# IotaWatt4_8.net
KiCad netlist of a schematic drawn in EAGLE
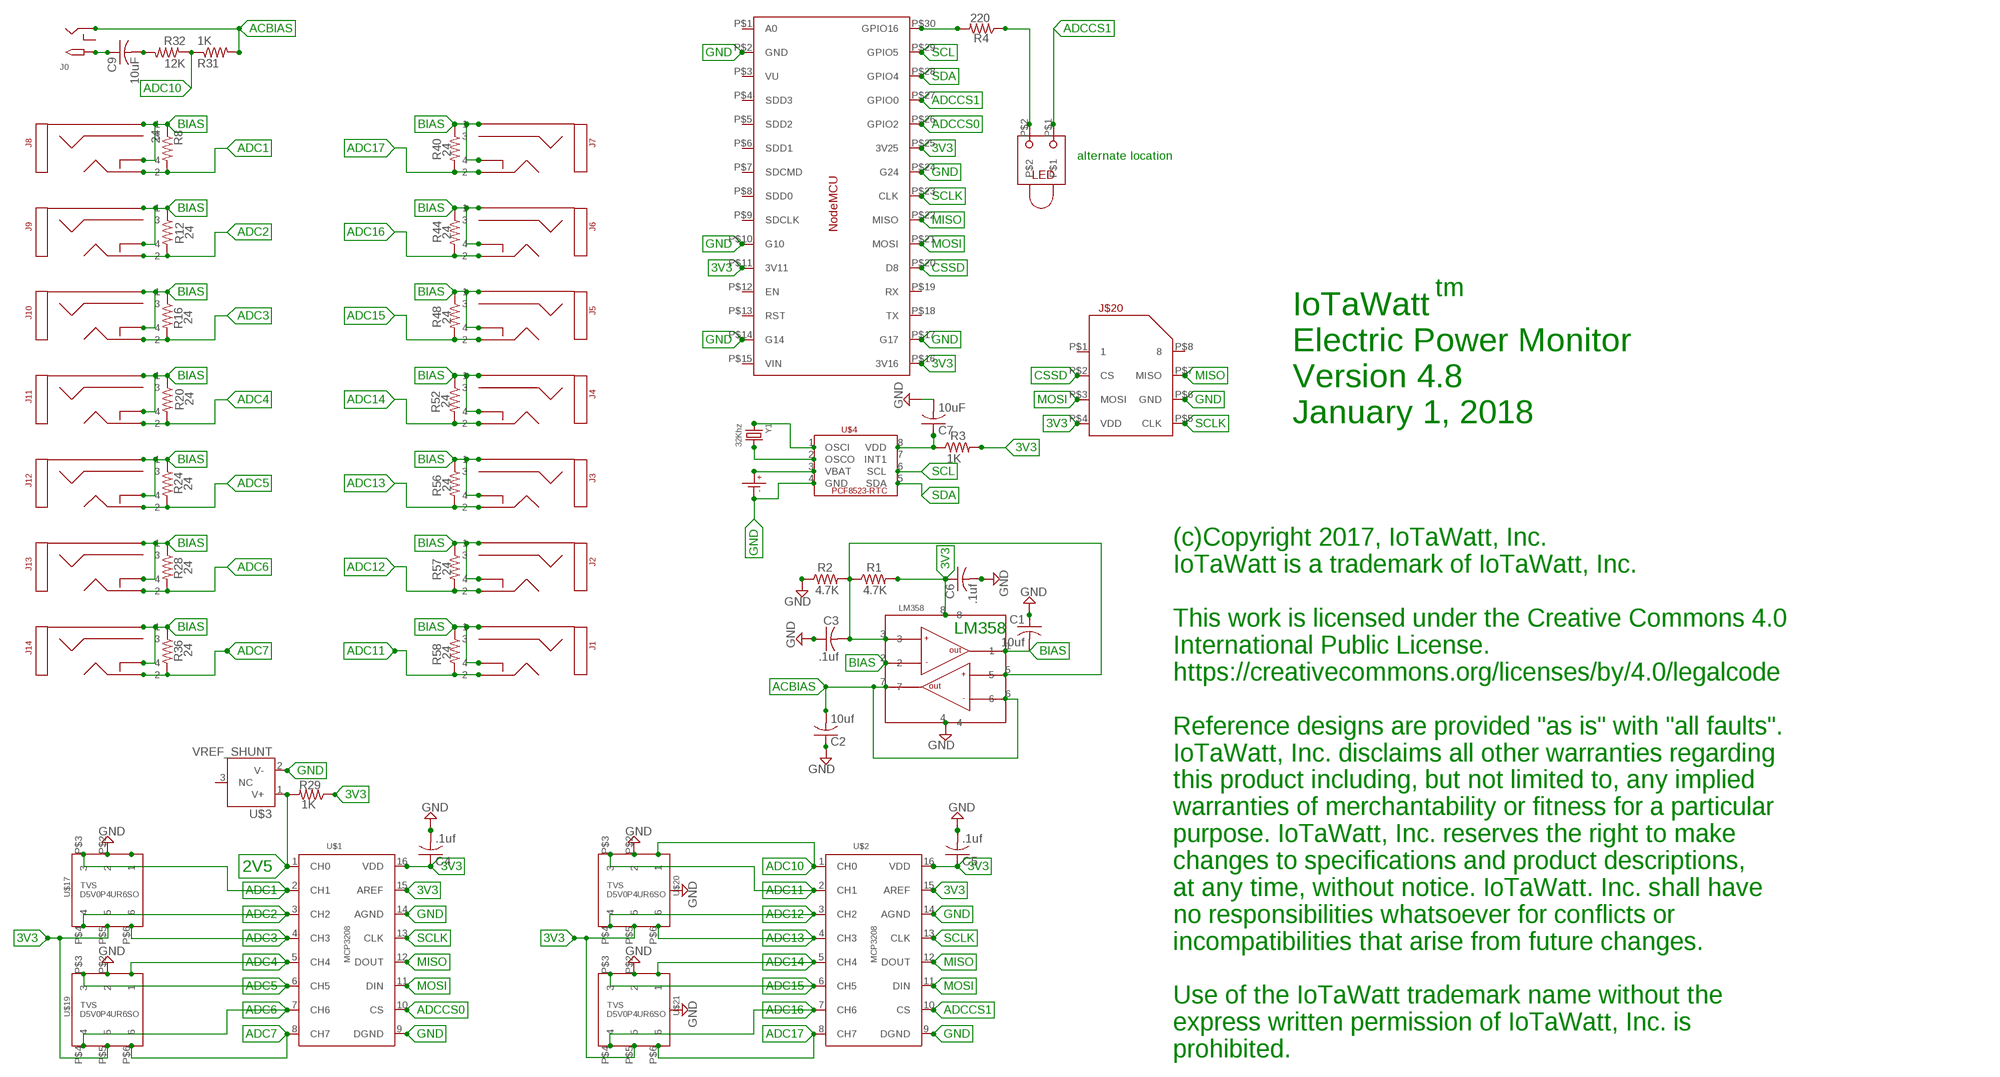
[diagram p0: schematic, sheet 1]

(export (version "E")
  (design (tool "Eeschema 10.0.6"))
  (components
    (comp (ref "C1")
      (value "10uf")
      (footprint "eagle-import:C0805")
      (libsource (lib "eagle-import") (part "C-USC0805"))
    )
    (comp (ref "C2")
      (value "10uf")
      (footprint "eagle-import:C0805")
      (libsource (lib "eagle-import") (part "C-USC0805"))
    )
    (comp (ref "C3")
      (value ".1uf")
      (footprint "eagle-import:C0805")
      (libsource (lib "eagle-import") (part "C-USC0805"))
    )
    (comp (ref "C4")
      (value ".1uf")
      (footprint "eagle-import:C0805")
      (libsource (lib "eagle-import") (part "C-USC0805"))
    )
    (comp (ref "C5")
      (value ".1uf")
      (footprint "eagle-import:C0805")
      (libsource (lib "eagle-import") (part "C-USC0805"))
    )
    (comp (ref "C6")
      (value ".1uf")
      (footprint "eagle-import:C0805")
      (libsource (lib "eagle-import") (part "C-USC0805"))
    )
    (comp (ref "C7")
      (value "10uF")
      (footprint "eagle-import:C0805")
      (libsource (lib "eagle-import") (part "C-USC0805"))
    )
    (comp (ref "C9")
      (value "10uF")
      (footprint "eagle-import:C0805")
      (libsource (lib "eagle-import") (part "C-USC0805"))
    )
    (comp (ref "J$20")
      (value "MICROSD_PUSH/PULL")
      (footprint "eagle-import:MICROSD")
      (libsource (lib "eagle-import") (part "MICROSD_PUSH/PULL"))
    )
    (comp (ref "J0")
      (value "2.1MMJACKSMT")
      (footprint "eagle-import:DCJACK_2MM_SMT")
      (libsource (lib "eagle-import") (part "2.1MMJACKSMT"))
    )
    (comp (ref "J1")
      (value "STEREO_SMD")
      (footprint "eagle-import:STEREO_SMT")
      (libsource (lib "eagle-import") (part "STEREO_SMD"))
    )
    (comp (ref "J2")
      (value "STEREO_SMD")
      (footprint "eagle-import:STEREO_SMT")
      (libsource (lib "eagle-import") (part "STEREO_SMD"))
    )
    (comp (ref "J3")
      (value "STEREO_SMD")
      (footprint "eagle-import:STEREO_SMT")
      (libsource (lib "eagle-import") (part "STEREO_SMD"))
    )
    (comp (ref "J4")
      (value "STEREO_SMD")
      (footprint "eagle-import:STEREO_SMT")
      (libsource (lib "eagle-import") (part "STEREO_SMD"))
    )
    (comp (ref "J5")
      (value "STEREO_SMD")
      (footprint "eagle-import:STEREO_SMT")
      (libsource (lib "eagle-import") (part "STEREO_SMD"))
    )
    (comp (ref "J6")
      (value "STEREO_SMD")
      (footprint "eagle-import:STEREO_SMT")
      (libsource (lib "eagle-import") (part "STEREO_SMD"))
    )
    (comp (ref "J7")
      (value "STEREO_SMD")
      (footprint "eagle-import:STEREO_SMT")
      (libsource (lib "eagle-import") (part "STEREO_SMD"))
    )
    (comp (ref "J8")
      (value "STEREO_SMD")
      (footprint "eagle-import:STEREO_SMT")
      (libsource (lib "eagle-import") (part "STEREO_SMD"))
    )
    (comp (ref "J9")
      (value "STEREO_SMD")
      (footprint "eagle-import:STEREO_SMT")
      (libsource (lib "eagle-import") (part "STEREO_SMD"))
    )
    (comp (ref "J10")
      (value "STEREO_SMD")
      (footprint "eagle-import:STEREO_SMT")
      (libsource (lib "eagle-import") (part "STEREO_SMD"))
    )
    (comp (ref "J11")
      (value "STEREO_SMD")
      (footprint "eagle-import:STEREO_SMT")
      (libsource (lib "eagle-import") (part "STEREO_SMD"))
    )
    (comp (ref "J12")
      (value "STEREO_SMD")
      (footprint "eagle-import:STEREO_SMT")
      (libsource (lib "eagle-import") (part "STEREO_SMD"))
    )
    (comp (ref "J13")
      (value "STEREO_SMD")
      (footprint "eagle-import:STEREO_SMT")
      (libsource (lib "eagle-import") (part "STEREO_SMD"))
    )
    (comp (ref "J14")
      (value "STEREO_SMD")
      (footprint "eagle-import:STEREO_SMT")
      (libsource (lib "eagle-import") (part "STEREO_SMD"))
    )
    (comp (ref "R1")
      (value "4.7K")
      (footprint "eagle-import:R0805")
      (libsource (lib "eagle-import") (part "R-US_R0805"))
    )
    (comp (ref "R2")
      (value "4.7K")
      (footprint "eagle-import:R0805")
      (libsource (lib "eagle-import") (part "R-US_R0805"))
    )
    (comp (ref "R3")
      (value "1K")
      (footprint "eagle-import:R0805")
      (libsource (lib "eagle-import") (part "R-US_R0805"))
    )
    (comp (ref "R4")
      (value "220")
      (footprint "eagle-import:R0805")
      (libsource (lib "eagle-import") (part "R-US_R0805"))
    )
    (comp (ref "R8")
      (value "24")
      (footprint "eagle-import:R0805")
      (libsource (lib "eagle-import") (part "R-US_R0805"))
    )
    (comp (ref "R12")
      (value "24")
      (footprint "eagle-import:R0805")
      (libsource (lib "eagle-import") (part "R-US_R0805"))
    )
    (comp (ref "R16")
      (value "24")
      (footprint "eagle-import:R0805")
      (libsource (lib "eagle-import") (part "R-US_R0805"))
    )
    (comp (ref "R20")
      (value "24")
      (footprint "eagle-import:R0805")
      (libsource (lib "eagle-import") (part "R-US_R0805"))
    )
    (comp (ref "R24")
      (value "24")
      (footprint "eagle-import:R0805")
      (libsource (lib "eagle-import") (part "R-US_R0805"))
    )
    (comp (ref "R28")
      (value "24")
      (footprint "eagle-import:R0805")
      (libsource (lib "eagle-import") (part "R-US_R0805"))
    )
    (comp (ref "R29")
      (value "1K")
      (footprint "eagle-import:R0805")
      (libsource (lib "eagle-import") (part "R-US_R0805"))
    )
    (comp (ref "R31")
      (value "1K")
      (footprint "eagle-import:R0805")
      (libsource (lib "eagle-import") (part "R-US_R0805"))
    )
    (comp (ref "R32")
      (value "12K")
      (footprint "eagle-import:R0805")
      (libsource (lib "eagle-import") (part "R-US_R0805"))
    )
    (comp (ref "R36")
      (value "24")
      (footprint "eagle-import:R0805")
      (libsource (lib "eagle-import") (part "R-US_R0805"))
    )
    (comp (ref "R40")
      (value "24")
      (footprint "eagle-import:R0805")
      (libsource (lib "eagle-import") (part "R-US_R0805"))
    )
    (comp (ref "R44")
      (value "24")
      (footprint "eagle-import:R0805")
      (libsource (lib "eagle-import") (part "R-US_R0805"))
    )
    (comp (ref "R48")
      (value "24")
      (footprint "eagle-import:R0805")
      (libsource (lib "eagle-import") (part "R-US_R0805"))
    )
    (comp (ref "R52")
      (value "24")
      (footprint "eagle-import:R0805")
      (libsource (lib "eagle-import") (part "R-US_R0805"))
    )
    (comp (ref "R56")
      (value "24")
      (footprint "eagle-import:R0805")
      (libsource (lib "eagle-import") (part "R-US_R0805"))
    )
    (comp (ref "R57")
      (value "24")
      (footprint "eagle-import:R0805")
      (libsource (lib "eagle-import") (part "R-US_R0805"))
    )
    (comp (ref "R58")
      (value "24")
      (footprint "eagle-import:R0805")
      (libsource (lib "eagle-import") (part "R-US_R0805"))
    )
    (comp (ref "U$1")
      (value "MCP3208")
      (footprint "eagle-import:SOIC_16")
      (libsource (lib "eagle-import") (part "MCP3208"))
    )
    (comp (ref "U$2")
      (value "MCP3208")
      (footprint "eagle-import:SOIC_16")
      (libsource (lib "eagle-import") (part "MCP3208"))
    )
    (comp (ref "U$3")
      (value "VREF_SHUNT")
      (footprint "eagle-import:SOT23_3")
      (libsource (lib "eagle-import") (part "VREF_SHUNT"))
    )
    (comp (ref "U$4")
      (value "PCF8523_RTC")
      (footprint "eagle-import:SOIC_8")
      (libsource (lib "eagle-import") (part "PCF8523_RTC"))
    )
    (comp (ref "U$16")
      (value "NODEMCU")
      (footprint "eagle-import:NODEMCU")
      (libsource (lib "eagle-import") (part "NODEMCU"))
    )
    (comp (ref "U$17")
      (value "TVS_4CHAN_ARRAYSC-74")
      (footprint "eagle-import:SC-74")
      (libsource (lib "eagle-import") (part "TVS_4CHAN_ARRAYSC-74"))
    )
    (comp (ref "U$18")
      (value "CR1220SMD")
      (footprint "eagle-import:CR1220SMD")
      (libsource (lib "eagle-import") (part "CR1220SMD"))
    )
    (comp (ref "U$19")
      (value "TVS_4CHAN_ARRAYSC-74")
      (footprint "eagle-import:SC-74")
      (libsource (lib "eagle-import") (part "TVS_4CHAN_ARRAYSC-74"))
    )
    (comp (ref "U$20")
      (value "TVS_4CHAN_ARRAYSC-74")
      (footprint "eagle-import:SC-74")
      (libsource (lib "eagle-import") (part "TVS_4CHAN_ARRAYSC-74"))
    )
    (comp (ref "U$21")
      (value "TVS_4CHAN_ARRAYSC-74")
      (footprint "eagle-import:SC-74")
      (libsource (lib "eagle-import") (part "TVS_4CHAN_ARRAYSC-74"))
    )
    (comp (ref "U$22")
      (value "LM358_DUAL_OP-AMP")
      (footprint "eagle-import:SOIC_8")
      (libsource (lib "eagle-import") (part "LM358_DUAL_OP-AMP"))
    )
    (comp (ref "U$23")
      (value "LED_RT_TRH")
      (footprint "eagle-import:LED_TH_RT")
      (libsource (lib "eagle-import") (part "LED_RT_TRH"))
    )
    (comp (ref "Y1")
      (value "32Khz")
      (footprint "eagle-import:CRYSTAL_8X3.8")
      (libsource (lib "eagle-import") (part "CRYSTAL8X3.8SMT"))
    )
  )
  (nets
    (net (code "1") (name "2V5") (class "Default")
      (node (ref "R29") (pin "2") (pinfunction "2_2") (pintype "passive"))
      (node (ref "U$1") (pin "1") (pinfunction "CH0_1") (pintype "input"))
      (node (ref "U$3") (pin "1") (pinfunction "V+_1") (pintype "bidirectional"))
    )
    (net (code "2") (name "3V3") (class "Default")
      (node (ref "C4") (pin "1") (pinfunction "1_1") (pintype "passive"))
      (node (ref "C5") (pin "1") (pinfunction "1_1") (pintype "passive"))
      (node (ref "C6") (pin "1") (pinfunction "1_1") (pintype "passive"))
      (node (ref "J$20") (pin "P$4") (pinfunction "VDD_P$4") (pintype "bidirectional"))
      (node (ref "R1") (pin "2") (pinfunction "2_2") (pintype "passive"))
      (node (ref "R29") (pin "1") (pinfunction "1_1") (pintype "passive"))
      (node (ref "R3") (pin "2") (pinfunction "2_2") (pintype "passive"))
      (node (ref "U$1") (pin "15") (pinfunction "AREF_15") (pintype "input"))
      (node (ref "U$1") (pin "16") (pinfunction "VDD_16") (pintype "bidirectional"))
      (node (ref "U$16") (pin "P$11") (pinfunction "3V11_P$11") (pintype "bidirectional"))
      (node (ref "U$16") (pin "P$16") (pinfunction "3V16_P$16") (pintype "bidirectional"))
      (node (ref "U$16") (pin "P$25") (pinfunction "3V25_P$25") (pintype "bidirectional"))
      (node (ref "U$17") (pin "P$5") (pinfunction "5_P$5") (pintype "bidirectional"))
      (node (ref "U$19") (pin "P$5") (pinfunction "5_P$5") (pintype "bidirectional"))
      (node (ref "U$2") (pin "15") (pinfunction "AREF_15") (pintype "input"))
      (node (ref "U$2") (pin "16") (pinfunction "VDD_16") (pintype "bidirectional"))
      (node (ref "U$20") (pin "P$5") (pinfunction "5_P$5") (pintype "bidirectional"))
      (node (ref "U$21") (pin "P$5") (pinfunction "5_P$5") (pintype "bidirectional"))
      (node (ref "U$22") (pin "8") (pinfunction "8_8") (pintype "bidirectional"))
    )
    (net (code "3") (name "ACBIAS") (class "Default")
      (node (ref "C2") (pin "2") (pinfunction "2_2") (pintype "passive"))
      (node (ref "J0") (pin "GND") (pinfunction "RING_GND") (pintype "bidirectional"))
      (node (ref "R31") (pin "2") (pinfunction "2_2") (pintype "passive"))
      (node (ref "U$22") (pin "6") (pinfunction "6_6") (pintype "bidirectional"))
      (node (ref "U$22") (pin "7") (pinfunction "7_7") (pintype "bidirectional"))
    )
    (net (code "4") (name "ADC1") (class "Default")
      (node (ref "J8") (pin "P$2") (pinfunction "2_P$2") (pintype "bidirectional"))
      (node (ref "R8") (pin "2") (pinfunction "2_2") (pintype "passive"))
      (node (ref "U$1") (pin "2") (pinfunction "CH1_2") (pintype "input"))
      (node (ref "U$17") (pin "P$3") (pinfunction "3_P$3") (pintype "bidirectional"))
    )
    (net (code "5") (name "ADC2") (class "Default")
      (node (ref "J9") (pin "P$2") (pinfunction "2_P$2") (pintype "bidirectional"))
      (node (ref "R12") (pin "2") (pinfunction "2_2") (pintype "passive"))
      (node (ref "U$1") (pin "3") (pinfunction "CH2_3") (pintype "input"))
      (node (ref "U$17") (pin "P$4") (pinfunction "4_P$4") (pintype "bidirectional"))
    )
    (net (code "6") (name "ADC3") (class "Default")
      (node (ref "J10") (pin "P$2") (pinfunction "2_P$2") (pintype "bidirectional"))
      (node (ref "R16") (pin "2") (pinfunction "2_2") (pintype "passive"))
      (node (ref "U$1") (pin "4") (pinfunction "CH3_4") (pintype "input"))
      (node (ref "U$17") (pin "P$6") (pinfunction "6_P$6") (pintype "bidirectional"))
    )
    (net (code "7") (name "ADC4") (class "Default")
      (node (ref "J11") (pin "P$2") (pinfunction "2_P$2") (pintype "bidirectional"))
      (node (ref "R20") (pin "2") (pinfunction "2_2") (pintype "passive"))
      (node (ref "U$1") (pin "5") (pinfunction "CH4_5") (pintype "bidirectional"))
      (node (ref "U$19") (pin "P$1") (pinfunction "1_P$1") (pintype "bidirectional"))
    )
    (net (code "8") (name "ADC5") (class "Default")
      (node (ref "J12") (pin "P$2") (pinfunction "2_P$2") (pintype "bidirectional"))
      (node (ref "R24") (pin "2") (pinfunction "2_2") (pintype "passive"))
      (node (ref "U$1") (pin "6") (pinfunction "CH5_6") (pintype "bidirectional"))
      (node (ref "U$19") (pin "P$3") (pinfunction "3_P$3") (pintype "bidirectional"))
    )
    (net (code "9") (name "ADC6") (class "Default")
      (node (ref "J13") (pin "P$2") (pinfunction "2_P$2") (pintype "bidirectional"))
      (node (ref "R28") (pin "2") (pinfunction "2_2") (pintype "passive"))
      (node (ref "U$1") (pin "7") (pinfunction "CH6_7") (pintype "input"))
      (node (ref "U$19") (pin "P$4") (pinfunction "4_P$4") (pintype "bidirectional"))
    )
    (net (code "10") (name "ADC7") (class "Default")
      (node (ref "J14") (pin "P$2") (pinfunction "2_P$2") (pintype "bidirectional"))
      (node (ref "R36") (pin "2") (pinfunction "2_2") (pintype "passive"))
      (node (ref "U$1") (pin "8") (pinfunction "CH7_8") (pintype "bidirectional"))
      (node (ref "U$19") (pin "P$6") (pinfunction "6_P$6") (pintype "bidirectional"))
    )
    (net (code "11") (name "ADC10") (class "Default")
      (node (ref "R31") (pin "1") (pinfunction "1_1") (pintype "passive"))
      (node (ref "R32") (pin "1") (pinfunction "1_1") (pintype "passive"))
      (node (ref "U$2") (pin "1") (pinfunction "CH0_1") (pintype "input"))
      (node (ref "U$20") (pin "P$1") (pinfunction "1_P$1") (pintype "bidirectional"))
    )
    (net (code "12") (name "ADC11") (class "Default")
      (node (ref "J1") (pin "P$2") (pinfunction "2_P$2") (pintype "bidirectional"))
      (node (ref "R58") (pin "2") (pinfunction "2_2") (pintype "passive"))
      (node (ref "U$2") (pin "2") (pinfunction "CH1_2") (pintype "input"))
      (node (ref "U$20") (pin "P$3") (pinfunction "3_P$3") (pintype "bidirectional"))
    )
    (net (code "13") (name "ADC12") (class "Default")
      (node (ref "J2") (pin "P$2") (pinfunction "2_P$2") (pintype "bidirectional"))
      (node (ref "R57") (pin "2") (pinfunction "2_2") (pintype "passive"))
      (node (ref "U$2") (pin "3") (pinfunction "CH2_3") (pintype "input"))
      (node (ref "U$20") (pin "P$4") (pinfunction "4_P$4") (pintype "bidirectional"))
    )
    (net (code "14") (name "ADC13") (class "Default")
      (node (ref "J3") (pin "P$2") (pinfunction "2_P$2") (pintype "bidirectional"))
      (node (ref "R56") (pin "2") (pinfunction "2_2") (pintype "passive"))
      (node (ref "U$2") (pin "4") (pinfunction "CH3_4") (pintype "input"))
      (node (ref "U$20") (pin "P$6") (pinfunction "6_P$6") (pintype "bidirectional"))
    )
    (net (code "15") (name "ADC14") (class "Default")
      (node (ref "J4") (pin "P$2") (pinfunction "2_P$2") (pintype "bidirectional"))
      (node (ref "R52") (pin "2") (pinfunction "2_2") (pintype "passive"))
      (node (ref "U$2") (pin "5") (pinfunction "CH4_5") (pintype "bidirectional"))
      (node (ref "U$21") (pin "P$1") (pinfunction "1_P$1") (pintype "bidirectional"))
    )
    (net (code "16") (name "ADC15") (class "Default")
      (node (ref "J5") (pin "P$2") (pinfunction "2_P$2") (pintype "bidirectional"))
      (node (ref "R48") (pin "2") (pinfunction "2_2") (pintype "passive"))
      (node (ref "U$2") (pin "6") (pinfunction "CH5_6") (pintype "bidirectional"))
      (node (ref "U$21") (pin "P$3") (pinfunction "3_P$3") (pintype "bidirectional"))
    )
    (net (code "17") (name "ADC16") (class "Default")
      (node (ref "J6") (pin "P$2") (pinfunction "2_P$2") (pintype "bidirectional"))
      (node (ref "R44") (pin "2") (pinfunction "2_2") (pintype "passive"))
      (node (ref "U$2") (pin "7") (pinfunction "CH6_7") (pintype "input"))
      (node (ref "U$21") (pin "P$4") (pinfunction "4_P$4") (pintype "bidirectional"))
    )
    (net (code "18") (name "ADC17") (class "Default")
      (node (ref "J7") (pin "P$2") (pinfunction "2_P$2") (pintype "bidirectional"))
      (node (ref "R40") (pin "2") (pinfunction "2_2") (pintype "passive"))
      (node (ref "U$2") (pin "8") (pinfunction "CH7_8") (pintype "bidirectional"))
      (node (ref "U$21") (pin "P$6") (pinfunction "6_P$6") (pintype "bidirectional"))
    )
    (net (code "19") (name "ADCCS0") (class "Default")
      (node (ref "U$1") (pin "10") (pinfunction "CS_10") (pintype "input"))
      (node (ref "U$16") (pin "P$26") (pinfunction "GPIO2_P$26") (pintype "bidirectional"))
    )
    (net (code "20") (name "ADCCS1") (class "Default")
      (node (ref "U$16") (pin "P$27") (pinfunction "GPIO0_P$27") (pintype "bidirectional"))
      (node (ref "U$2") (pin "10") (pinfunction "CS_10") (pintype "input"))
      (node (ref "U$23") (pin "P$1") (pinfunction "P$1_P$1") (pintype "bidirectional"))
    )
    (net (code "21") (name "BIAS") (class "Default")
      (node (ref "C1") (pin "2") (pinfunction "2_2") (pintype "passive"))
      (node (ref "J1") (pin "P$1") (pinfunction "1_P$1") (pintype "bidirectional"))
      (node (ref "J1") (pin "P$4") (pinfunction "4_P$4") (pintype "bidirectional"))
      (node (ref "J10") (pin "P$1") (pinfunction "1_P$1") (pintype "bidirectional"))
      (node (ref "J10") (pin "P$4") (pinfunction "4_P$4") (pintype "bidirectional"))
      (node (ref "J11") (pin "P$1") (pinfunction "1_P$1") (pintype "bidirectional"))
      (node (ref "J11") (pin "P$4") (pinfunction "4_P$4") (pintype "bidirectional"))
      (node (ref "J12") (pin "P$1") (pinfunction "1_P$1") (pintype "bidirectional"))
      (node (ref "J12") (pin "P$4") (pinfunction "4_P$4") (pintype "bidirectional"))
      (node (ref "J13") (pin "P$1") (pinfunction "1_P$1") (pintype "bidirectional"))
      (node (ref "J13") (pin "P$4") (pinfunction "4_P$4") (pintype "bidirectional"))
      (node (ref "J14") (pin "P$1") (pinfunction "1_P$1") (pintype "bidirectional"))
      (node (ref "J14") (pin "P$4") (pinfunction "4_P$4") (pintype "bidirectional"))
      (node (ref "J2") (pin "P$1") (pinfunction "1_P$1") (pintype "bidirectional"))
      (node (ref "J2") (pin "P$4") (pinfunction "4_P$4") (pintype "bidirectional"))
      (node (ref "J3") (pin "P$1") (pinfunction "1_P$1") (pintype "bidirectional"))
      (node (ref "J3") (pin "P$4") (pinfunction "4_P$4") (pintype "bidirectional"))
      (node (ref "J4") (pin "P$1") (pinfunction "1_P$1") (pintype "bidirectional"))
      (node (ref "J4") (pin "P$4") (pinfunction "4_P$4") (pintype "bidirectional"))
      (node (ref "J5") (pin "P$1") (pinfunction "1_P$1") (pintype "bidirectional"))
      (node (ref "J5") (pin "P$4") (pinfunction "4_P$4") (pintype "bidirectional"))
      (node (ref "J6") (pin "P$1") (pinfunction "1_P$1") (pintype "bidirectional"))
      (node (ref "J6") (pin "P$4") (pinfunction "4_P$4") (pintype "bidirectional"))
      (node (ref "J7") (pin "P$1") (pinfunction "1_P$1") (pintype "bidirectional"))
      (node (ref "J7") (pin "P$4") (pinfunction "4_P$4") (pintype "bidirectional"))
      (node (ref "J8") (pin "P$1") (pinfunction "1_P$1") (pintype "bidirectional"))
      (node (ref "J8") (pin "P$4") (pinfunction "4_P$4") (pintype "bidirectional"))
      (node (ref "J9") (pin "P$1") (pinfunction "1_P$1") (pintype "bidirectional"))
      (node (ref "J9") (pin "P$4") (pinfunction "4_P$4") (pintype "bidirectional"))
      (node (ref "R12") (pin "1") (pinfunction "1_1") (pintype "passive"))
      (node (ref "R16") (pin "1") (pinfunction "1_1") (pintype "passive"))
      (node (ref "R20") (pin "1") (pinfunction "1_1") (pintype "passive"))
      (node (ref "R24") (pin "1") (pinfunction "1_1") (pintype "passive"))
      (node (ref "R28") (pin "1") (pinfunction "1_1") (pintype "passive"))
      (node (ref "R36") (pin "1") (pinfunction "1_1") (pintype "passive"))
      (node (ref "R40") (pin "1") (pinfunction "1_1") (pintype "passive"))
      (node (ref "R44") (pin "1") (pinfunction "1_1") (pintype "passive"))
      (node (ref "R48") (pin "1") (pinfunction "1_1") (pintype "passive"))
      (node (ref "R52") (pin "1") (pinfunction "1_1") (pintype "passive"))
      (node (ref "R56") (pin "1") (pinfunction "1_1") (pintype "passive"))
      (node (ref "R57") (pin "1") (pinfunction "1_1") (pintype "passive"))
      (node (ref "R58") (pin "1") (pinfunction "1_1") (pintype "passive"))
      (node (ref "R8") (pin "1") (pinfunction "1_1") (pintype "passive"))
      (node (ref "U$22") (pin "1") (pinfunction "1_1") (pintype "bidirectional"))
      (node (ref "U$22") (pin "2") (pinfunction "2_2") (pintype "bidirectional"))
    )
    (net (code "22") (name "CSSD") (class "Default")
      (node (ref "J$20") (pin "P$2") (pinfunction "CS_P$2") (pintype "bidirectional"))
      (node (ref "U$16") (pin "P$20") (pinfunction "D8_P$20") (pintype "bidirectional"))
    )
    (net (code "23") (name "GND") (class "Default")
      (node (ref "C1") (pin "1") (pinfunction "1_1") (pintype "passive"))
      (node (ref "C2") (pin "1") (pinfunction "1_1") (pintype "passive"))
      (node (ref "C3") (pin "1") (pinfunction "1_1") (pintype "passive"))
      (node (ref "C4") (pin "2") (pinfunction "2_2") (pintype "passive"))
      (node (ref "C5") (pin "2") (pinfunction "2_2") (pintype "passive"))
      (node (ref "C6") (pin "2") (pinfunction "2_2") (pintype "passive"))
      (node (ref "C7") (pin "2") (pinfunction "2_2") (pintype "passive"))
      (node (ref "J$20") (pin "P$6") (pinfunction "GND_P$6") (pintype "bidirectional"))
      (node (ref "R2") (pin "1") (pinfunction "1_1") (pintype "passive"))
      (node (ref "U$1") (pin "14") (pinfunction "AGND_14") (pintype "input"))
      (node (ref "U$1") (pin "9") (pinfunction "DGND_9") (pintype "bidirectional"))
      (node (ref "U$16") (pin "P$10") (pinfunction "G10_P$10") (pintype "bidirectional"))
      (node (ref "U$16") (pin "P$14") (pinfunction "G14_P$14") (pintype "bidirectional"))
      (node (ref "U$16") (pin "P$17") (pinfunction "G17_P$17") (pintype "bidirectional"))
      (node (ref "U$16") (pin "P$2") (pinfunction "GND_P$2") (pintype "bidirectional"))
      (node (ref "U$16") (pin "P$24") (pinfunction "G24_P$24") (pintype "bidirectional"))
      (node (ref "U$17") (pin "P$2") (pinfunction "2_P$2") (pintype "bidirectional"))
      (node (ref "U$18") (pin "P-") (pinfunction "P$-_P-") (pintype "bidirectional"))
      (node (ref "U$19") (pin "P$2") (pinfunction "2_P$2") (pintype "bidirectional"))
      (node (ref "U$2") (pin "14") (pinfunction "AGND_14") (pintype "input"))
      (node (ref "U$2") (pin "9") (pinfunction "DGND_9") (pintype "bidirectional"))
      (node (ref "U$20") (pin "P$2") (pinfunction "2_P$2") (pintype "bidirectional"))
      (node (ref "U$21") (pin "P$2") (pinfunction "2_P$2") (pintype "bidirectional"))
      (node (ref "U$22") (pin "4") (pinfunction "4_4") (pintype "bidirectional"))
      (node (ref "U$3") (pin "2") (pinfunction "V-_2") (pintype "bidirectional"))
      (node (ref "U$4") (pin "4") (pinfunction "GND_4") (pintype "bidirectional"))
    )
    (net (code "24") (name "MISO") (class "Default")
      (node (ref "J$20") (pin "P$7") (pinfunction "MISO_P$7") (pintype "bidirectional"))
      (node (ref "U$1") (pin "12") (pinfunction "DOUT_12") (pintype "bidirectional"))
      (node (ref "U$16") (pin "P$22") (pinfunction "MISO_P$22") (pintype "bidirectional"))
      (node (ref "U$2") (pin "12") (pinfunction "DOUT_12") (pintype "bidirectional"))
    )
    (net (code "25") (name "MOSI") (class "Default")
      (node (ref "J$20") (pin "P$3") (pinfunction "MOSI_P$3") (pintype "bidirectional"))
      (node (ref "U$1") (pin "11") (pinfunction "DIN_11") (pintype "input"))
      (node (ref "U$16") (pin "P$21") (pinfunction "MOSI_P$21") (pintype "bidirectional"))
      (node (ref "U$2") (pin "11") (pinfunction "DIN_11") (pintype "input"))
    )
    (net (code "26") (name "Net-(C3-Pad2)") (class "Default")
      (node (ref "C3") (pin "2") (pinfunction "2_2") (pintype "passive"))
      (node (ref "R1") (pin "1") (pinfunction "1_1") (pintype "passive"))
      (node (ref "R2") (pin "2") (pinfunction "2_2") (pintype "passive"))
      (node (ref "U$22") (pin "3") (pinfunction "3_3") (pintype "bidirectional"))
      (node (ref "U$22") (pin "5") (pinfunction "5_5") (pintype "bidirectional"))
    )
    (net (code "27") (name "Net-(C9-Pad2)") (class "Default")
      (node (ref "C9") (pin "2") (pinfunction "2_2") (pintype "passive"))
      (node (ref "R32") (pin "2") (pinfunction "2_2") (pintype "passive"))
    )
    (net (code "28") (name "Net-(J0-TIP)") (class "Default")
      (node (ref "C9") (pin "1") (pinfunction "1_1") (pintype "passive"))
      (node (ref "J0") (pin "PWR2") (pinfunction "TIP_PWR2") (pintype "bidirectional"))
    )
    (net (code "29") (name "Net-(R4-Pad1)") (class "Default")
      (node (ref "R4") (pin "1") (pinfunction "1_1") (pintype "passive"))
      (node (ref "U$23") (pin "P$2") (pinfunction "P$2_P$2") (pintype "bidirectional"))
    )
    (net (code "30") (name "Net-(U$4-OSCI)") (class "Default")
      (node (ref "U$4") (pin "1") (pinfunction "OSCI_1") (pintype "bidirectional"))
      (node (ref "Y1") (pin "P$1") (pinfunction "1_P$1") (pintype "passive"))
    )
    (net (code "31") (name "Net-(U$4-OSCO)") (class "Default")
      (node (ref "U$4") (pin "2") (pinfunction "OSCO_2") (pintype "bidirectional"))
      (node (ref "Y1") (pin "P$4") (pinfunction "2_P$4") (pintype "passive"))
    )
    (net (code "32") (name "Net-(U$4-VDD)") (class "Default")
      (node (ref "C7") (pin "1") (pinfunction "1_1") (pintype "passive"))
      (node (ref "R3") (pin "1") (pinfunction "1_1") (pintype "passive"))
      (node (ref "U$4") (pin "8") (pinfunction "VDD_8") (pintype "bidirectional"))
    )
    (net (code "33") (name "Net-(U$16-GPIO16)") (class "Default")
      (node (ref "R4") (pin "2") (pinfunction "2_2") (pintype "passive"))
      (node (ref "U$16") (pin "P$30") (pinfunction "GPIO16_P$30") (pintype "bidirectional"))
    )
    (net (code "34") (name "Net-(U$18-P$+)") (class "Default")
      (node (ref "U$18") (pin "P+") (pinfunction "P$+_P+") (pintype "bidirectional"))
      (node (ref "U$4") (pin "3") (pinfunction "VBAT_3") (pintype "bidirectional"))
    )
    (net (code "35") (name "SCL") (class "Default")
      (node (ref "U$16") (pin "P$29") (pinfunction "GPIO5_P$29") (pintype "bidirectional"))
      (node (ref "U$4") (pin "6") (pinfunction "SCL_6") (pintype "bidirectional"))
    )
    (net (code "36") (name "SCLK") (class "Default")
      (node (ref "J$20") (pin "P$5") (pinfunction "CLK_P$5") (pintype "bidirectional"))
      (node (ref "U$1") (pin "13") (pinfunction "CLK_13") (pintype "input"))
      (node (ref "U$16") (pin "P$23") (pinfunction "CLK_P$23") (pintype "bidirectional"))
      (node (ref "U$2") (pin "13") (pinfunction "CLK_13") (pintype "input"))
    )
    (net (code "37") (name "SDA") (class "Default")
      (node (ref "U$16") (pin "P$28") (pinfunction "GPIO4_P$28") (pintype "bidirectional"))
      (node (ref "U$4") (pin "5") (pinfunction "SDA_5") (pintype "bidirectional"))
    )
    (net (code "38") (name "unconnected-(J$20-1-PadP$1)") (class "Default")
      (node (ref "J$20") (pin "P$1") (pinfunction "1_P$1") (pintype "bidirectional"))
    )
    (net (code "39") (name "unconnected-(J$20-8-PadP$8)") (class "Default")
      (node (ref "J$20") (pin "P$8") (pinfunction "8_P$8") (pintype "bidirectional"))
    )
    (net (code "40") (name "unconnected-(J0-RING_SW-PadGNDBREAK)") (class "Default")
      (node (ref "J0") (pin "GNDBREAK") (pinfunction "RING_SW_GNDBREAK") (pintype "bidirectional"))
    )
    (net (code "41") (name "unconnected-(J1-3-PadP$3)") (class "Default")
      (node (ref "J1") (pin "P$3") (pinfunction "3_P$3") (pintype "bidirectional"))
    )
    (net (code "42") (name "unconnected-(J2-3-PadP$3)") (class "Default")
      (node (ref "J2") (pin "P$3") (pinfunction "3_P$3") (pintype "bidirectional"))
    )
    (net (code "43") (name "unconnected-(J3-3-PadP$3)") (class "Default")
      (node (ref "J3") (pin "P$3") (pinfunction "3_P$3") (pintype "bidirectional"))
    )
    (net (code "44") (name "unconnected-(J4-3-PadP$3)") (class "Default")
      (node (ref "J4") (pin "P$3") (pinfunction "3_P$3") (pintype "bidirectional"))
    )
    (net (code "45") (name "unconnected-(J5-3-PadP$3)") (class "Default")
      (node (ref "J5") (pin "P$3") (pinfunction "3_P$3") (pintype "bidirectional"))
    )
    (net (code "46") (name "unconnected-(J6-3-PadP$3)") (class "Default")
      (node (ref "J6") (pin "P$3") (pinfunction "3_P$3") (pintype "bidirectional"))
    )
    (net (code "47") (name "unconnected-(J7-3-PadP$3)") (class "Default")
      (node (ref "J7") (pin "P$3") (pinfunction "3_P$3") (pintype "bidirectional"))
    )
    (net (code "48") (name "unconnected-(J8-3-PadP$3)") (class "Default")
      (node (ref "J8") (pin "P$3") (pinfunction "3_P$3") (pintype "bidirectional"))
    )
    (net (code "49") (name "unconnected-(J9-3-PadP$3)") (class "Default")
      (node (ref "J9") (pin "P$3") (pinfunction "3_P$3") (pintype "bidirectional"))
    )
    (net (code "50") (name "unconnected-(J10-3-PadP$3)") (class "Default")
      (node (ref "J10") (pin "P$3") (pinfunction "3_P$3") (pintype "bidirectional"))
    )
    (net (code "51") (name "unconnected-(J11-3-PadP$3)") (class "Default")
      (node (ref "J11") (pin "P$3") (pinfunction "3_P$3") (pintype "bidirectional"))
    )
    (net (code "52") (name "unconnected-(J12-3-PadP$3)") (class "Default")
      (node (ref "J12") (pin "P$3") (pinfunction "3_P$3") (pintype "bidirectional"))
    )
    (net (code "53") (name "unconnected-(J13-3-PadP$3)") (class "Default")
      (node (ref "J13") (pin "P$3") (pinfunction "3_P$3") (pintype "bidirectional"))
    )
    (net (code "54") (name "unconnected-(J14-3-PadP$3)") (class "Default")
      (node (ref "J14") (pin "P$3") (pinfunction "3_P$3") (pintype "bidirectional"))
    )
    (net (code "55") (name "unconnected-(U$3-NC-Pad3)") (class "Default")
      (node (ref "U$3") (pin "3") (pinfunction "NC_3") (pintype "bidirectional"))
    )
    (net (code "56") (name "unconnected-(U$4-INT1-Pad7)") (class "Default")
      (node (ref "U$4") (pin "7") (pinfunction "INT1_7") (pintype "bidirectional"))
    )
    (net (code "57") (name "unconnected-(U$16-A0-PadP$1)") (class "Default")
      (node (ref "U$16") (pin "P$1") (pinfunction "A0_P$1") (pintype "bidirectional"))
    )
    (net (code "58") (name "unconnected-(U$16-EN-PadP$12)") (class "Default")
      (node (ref "U$16") (pin "P$12") (pinfunction "EN_P$12") (pintype "bidirectional"))
    )
    (net (code "59") (name "unconnected-(U$16-RST-PadP$13)") (class "Default")
      (node (ref "U$16") (pin "P$13") (pinfunction "RST_P$13") (pintype "bidirectional"))
    )
    (net (code "60") (name "unconnected-(U$16-RX-PadP$19)") (class "Default")
      (node (ref "U$16") (pin "P$19") (pinfunction "RX_P$19") (pintype "bidirectional"))
    )
    (net (code "61") (name "unconnected-(U$16-SDCLK-PadP$9)") (class "Default")
      (node (ref "U$16") (pin "P$9") (pinfunction "SDCLK_P$9") (pintype "bidirectional"))
    )
    (net (code "62") (name "unconnected-(U$16-SDCMD-PadP$7)") (class "Default")
      (node (ref "U$16") (pin "P$7") (pinfunction "SDCMD_P$7") (pintype "bidirectional"))
    )
    (net (code "63") (name "unconnected-(U$16-SDD0-PadP$8)") (class "Default")
      (node (ref "U$16") (pin "P$8") (pinfunction "SDD0_P$8") (pintype "bidirectional"))
    )
    (net (code "64") (name "unconnected-(U$16-SDD1-PadP$6)") (class "Default")
      (node (ref "U$16") (pin "P$6") (pinfunction "SDD1_P$6") (pintype "bidirectional"))
    )
    (net (code "65") (name "unconnected-(U$16-SDD2-PadP$5)") (class "Default")
      (node (ref "U$16") (pin "P$5") (pinfunction "SDD2_P$5") (pintype "bidirectional"))
    )
    (net (code "66") (name "unconnected-(U$16-SDD3-PadP$4)") (class "Default")
      (node (ref "U$16") (pin "P$4") (pinfunction "SDD3_P$4") (pintype "bidirectional"))
    )
    (net (code "67") (name "unconnected-(U$16-TX-PadP$18)") (class "Default")
      (node (ref "U$16") (pin "P$18") (pinfunction "TX_P$18") (pintype "bidirectional"))
    )
    (net (code "68") (name "unconnected-(U$16-VIN-PadP$15)") (class "Default")
      (node (ref "U$16") (pin "P$15") (pinfunction "VIN_P$15") (pintype "bidirectional"))
    )
    (net (code "69") (name "unconnected-(U$16-VU-PadP$3)") (class "Default")
      (node (ref "U$16") (pin "P$3") (pinfunction "VU_P$3") (pintype "bidirectional"))
    )
    (net (code "70") (name "unconnected-(U$17-1-PadP$1)") (class "Default")
      (node (ref "U$17") (pin "P$1") (pinfunction "1_P$1") (pintype "bidirectional"))
    )
  )
)
